# camera.net
KiCad netlist of a schematic drawn in Altium Designer
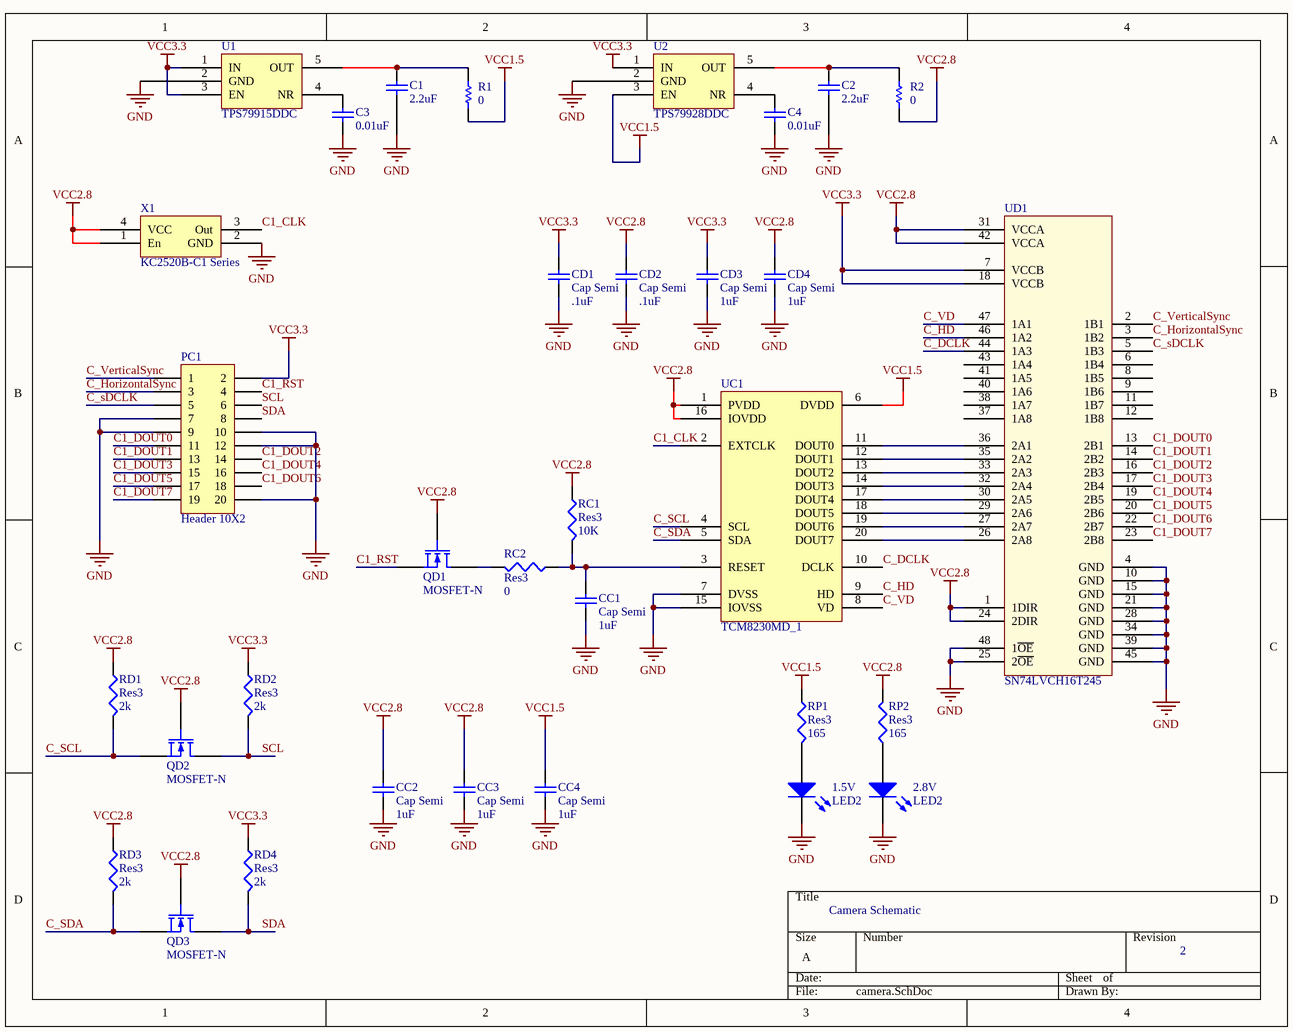
[diagram p0: camera.SchDoc]

(export (version "E")
  (design (tool "Eeschema 10.0.6"))
  (components
    (comp (ref "1.5V")
      (value "LED2")
      (footprint "DIODE1608")
      (description "Typical RED, GREEN, YELLOW, AMBER GaAs LED")
      (fields (field (name "PUBLISHER") "Altium Limited"))
      (libsource (lib "Miscellaneous Devices") (part "LED2"))
    )
    (comp (ref "2.8V")
      (value "LED2")
      (footprint "DIODE1608")
      (description "Typical RED, GREEN, YELLOW, AMBER GaAs LED")
      (fields (field (name "PUBLISHER") "Altium Limited"))
      (libsource (lib "Miscellaneous Devices") (part "LED2"))
    )
    (comp (ref "C1")
      (value "2.2uF")
      (footprint "CAPC1608L")
      (description "Capacitor (Semiconductor SIM Model)")
      (fields (field (name "Comment") "Cap Semi") (field (name "PUBLISHER") "Altium Limited"))
      (libsource (lib "Miscellaneous Devices") (part "Cap Semi"))
    )
    (comp (ref "C2")
      (value "2.2uF")
      (footprint "CAPC1608L")
      (description "Capacitor (Semiconductor SIM Model)")
      (fields (field (name "Comment") "Cap Semi") (field (name "PUBLISHER") "Altium Limited"))
      (libsource (lib "Miscellaneous Devices") (part "Cap Semi"))
    )
    (comp (ref "C3")
      (value "0.01uF")
      (footprint "CAPC1608L")
      (description "Capacitor (Semiconductor SIM Model)")
      (fields (field (name "Comment") "Cap Semi") (field (name "PUBLISHER") "Altium Limited"))
      (libsource (lib "Miscellaneous Devices") (part "Cap Semi"))
    )
    (comp (ref "C4")
      (value "0.01uF")
      (footprint "CAPC1608L")
      (description "Capacitor (Semiconductor SIM Model)")
      (fields (field (name "Comment") "Cap Semi") (field (name "PUBLISHER") "Altium Limited"))
      (libsource (lib "Miscellaneous Devices") (part "Cap Semi"))
    )
    (comp (ref "CC1")
      (value "Cap Semi")
      (footprint "CAPC1608L")
      (description "Capacitor (Semiconductor SIM Model)")
      (fields (field (name "ALTIUM_VALUE") "1uF") (field (name "PUBLISHER") "Altium Limited"))
      (libsource (lib "Miscellaneous Devices") (part "Cap Semi"))
    )
    (comp (ref "CC2")
      (value "Cap Semi")
      (footprint "CAPC1608L")
      (description "Capacitor (Semiconductor SIM Model)")
      (fields (field (name "ALTIUM_VALUE") "1uF") (field (name "PUBLISHER") "Altium Limited"))
      (libsource (lib "Miscellaneous Devices") (part "Cap Semi"))
    )
    (comp (ref "CC3")
      (value "Cap Semi")
      (footprint "CAPC1608L")
      (description "Capacitor (Semiconductor SIM Model)")
      (fields (field (name "ALTIUM_VALUE") "1uF") (field (name "PUBLISHER") "Altium Limited"))
      (libsource (lib "Miscellaneous Devices") (part "Cap Semi"))
    )
    (comp (ref "CC4")
      (value "Cap Semi")
      (footprint "CAPC1608L")
      (description "Capacitor (Semiconductor SIM Model)")
      (fields (field (name "ALTIUM_VALUE") "1uF") (field (name "PUBLISHER") "Altium Limited"))
      (libsource (lib "Miscellaneous Devices") (part "Cap Semi"))
    )
    (comp (ref "CD1")
      (value "Cap Semi")
      (footprint "CAPC1608L")
      (description "Capacitor (Semiconductor SIM Model)")
      (fields (field (name "ALTIUM_VALUE") ".1uF") (field (name "PUBLISHER") "Altium Limited"))
      (libsource (lib "Miscellaneous Devices") (part "Cap Semi"))
    )
    (comp (ref "CD2")
      (value "Cap Semi")
      (footprint "CAPC1608L")
      (description "Capacitor (Semiconductor SIM Model)")
      (fields (field (name "ALTIUM_VALUE") ".1uF") (field (name "PUBLISHER") "Altium Limited"))
      (libsource (lib "Miscellaneous Devices") (part "Cap Semi"))
    )
    (comp (ref "CD3")
      (value "Cap Semi")
      (footprint "CAPC1608L")
      (description "Capacitor (Semiconductor SIM Model)")
      (fields (field (name "ALTIUM_VALUE") "1uF") (field (name "PUBLISHER") "Altium Limited"))
      (libsource (lib "Miscellaneous Devices") (part "Cap Semi"))
    )
    (comp (ref "CD4")
      (value "Cap Semi")
      (footprint "CAPC1608L")
      (description "Capacitor (Semiconductor SIM Model)")
      (fields (field (name "ALTIUM_VALUE") "1uF") (field (name "PUBLISHER") "Altium Limited"))
      (libsource (lib "Miscellaneous Devices") (part "Cap Semi"))
    )
    (comp (ref "PC1")
      (value "Header 10X2")
      (footprint "HDR2X10")
      (description "Header, 10-Pin, Dual row")
      (fields (field (name "PUBLISHER") "Altium Limited"))
      (libsource (lib "Miscellaneous Connectors") (part "Header 10X2"))
    )
    (comp (ref "QD1")
      (value "MOSFET-N")
      (footprint "SOT95P240-3N")
      (description "N-Channel MOSFET")
      (fields (field (name "PUBLISHER") "Altium Limited"))
      (libsource (lib "Miscellaneous Devices") (part "MOSFET-N"))
    )
    (comp (ref "QD2")
      (value "MOSFET-N")
      (footprint "SOT95P240-3N")
      (description "N-Channel MOSFET")
      (fields (field (name "PUBLISHER") "Altium Limited"))
      (libsource (lib "Miscellaneous Devices") (part "MOSFET-N"))
    )
    (comp (ref "QD3")
      (value "MOSFET-N")
      (footprint "SOT95P240-3N")
      (description "N-Channel MOSFET")
      (fields (field (name "PUBLISHER") "Altium Limited"))
      (libsource (lib "Miscellaneous Devices") (part "MOSFET-N"))
    )
    (comp (ref "R1")
      (value "0")
      (footprint "RESC1608L")
      (description "Semiconductor Resistor")
      (fields (field (name "Comment") "Res Semi") (field (name "PUBLISHER") "Altium Limited"))
      (libsource (lib "Miscellaneous Devices") (part "Res Semi"))
    )
    (comp (ref "R2")
      (value "0")
      (footprint "RESC1608L")
      (description "Semiconductor Resistor")
      (fields (field (name "Comment") "Res Semi") (field (name "PUBLISHER") "Altium Limited"))
      (libsource (lib "Miscellaneous Devices") (part "Res Semi"))
    )
    (comp (ref "RC1")
      (value "Res3")
      (footprint "RESC1608L")
      (description "Resistor")
      (fields (field (name "ALTIUM_VALUE") "10K") (field (name "PUBLISHER") "Altium Limited"))
      (libsource (lib "Miscellaneous Devices") (part "Res3"))
    )
    (comp (ref "RC2")
      (value "Res3")
      (footprint "RESC1608L")
      (description "Resistor")
      (fields (field (name "ALTIUM_VALUE") "0") (field (name "PUBLISHER") "Altium Limited"))
      (libsource (lib "Miscellaneous Devices") (part "Res3"))
    )
    (comp (ref "RD1")
      (value "Res3")
      (footprint "RESC1608L")
      (description "Resistor")
      (fields (field (name "ALTIUM_VALUE") "2k") (field (name "PUBLISHER") "Altium Limited"))
      (libsource (lib "Miscellaneous Devices") (part "Res3"))
    )
    (comp (ref "RD2")
      (value "Res3")
      (footprint "RESC1608L")
      (description "Resistor")
      (fields (field (name "ALTIUM_VALUE") "2k") (field (name "PUBLISHER") "Altium Limited"))
      (libsource (lib "Miscellaneous Devices") (part "Res3"))
    )
    (comp (ref "RD3")
      (value "Res3")
      (footprint "RESC1608L")
      (description "Resistor")
      (fields (field (name "ALTIUM_VALUE") "2k") (field (name "PUBLISHER") "Altium Limited"))
      (libsource (lib "Miscellaneous Devices") (part "Res3"))
    )
    (comp (ref "RD4")
      (value "Res3")
      (footprint "RESC1608L")
      (description "Resistor")
      (fields (field (name "ALTIUM_VALUE") "2k") (field (name "PUBLISHER") "Altium Limited"))
      (libsource (lib "Miscellaneous Devices") (part "Res3"))
    )
    (comp (ref "RP1")
      (value "Res3")
      (footprint "RESC1608L")
      (description "Resistor")
      (fields (field (name "ALTIUM_VALUE") "165") (field (name "PUBLISHER") "Altium Limited"))
      (libsource (lib "Miscellaneous Devices") (part "Res3"))
    )
    (comp (ref "RP2")
      (value "Res3")
      (footprint "RESC1608L")
      (description "Resistor")
      (fields (field (name "ALTIUM_VALUE") "165") (field (name "PUBLISHER") "Altium Limited"))
      (libsource (lib "Miscellaneous Devices") (part "Res3"))
    )
    (comp (ref "U1")
      (value "TPS79915DDC")
      (footprint "TSOT23-5")
      (description "200mA, Low Quiescent Current, Ultra-Low Noise, High PSRR  Low Dropout Linear Regulator")
      (libsource (lib "Capstone_Lib") (part "TPS799xxDDC"))
    )
    (comp (ref "U2")
      (value "TPS79928DDC")
      (footprint "TSOT23-5")
      (description "200mA, Low Quiescent Current, Ultra-Low Noise, High PSRR  Low Dropout Linear Regulator")
      (libsource (lib "Capstone_Lib") (part "TPS799xxDDC"))
    )
    (comp (ref "UC1")
      (value "TCM8230MD_1")
      (footprint "TCM8230MD")
      (description "VGA CAMERA MODULE 640x480")
      (libsource (lib "daughterboard") (part "TCM8230MD_1"))
    )
    (comp (ref "UD1")
      (value "SN74LVCH16T245")
      (footprint "SN74LVCH16T245")
      (description "16-bit bus transceiver with voltage regulation.")
      (libsource (lib "daughterboard") (part "SN74LVCH16T245"))
    )
    (comp (ref "X1")
      (value "KC2520B-C1 Series")
      (footprint "KC2520B-C1")
      (description "Standard Oscillator")
      (libsource (lib "Capstone_Lib") (part "KC2520B-C1"))
    )
  )
  (nets
    (net (code "1") (name "/C1_CLK") (class "Default")
      (node (ref "UC1") (pin "2") (pinfunction "EXTCLK_2") (pintype "passive"))
      (node (ref "X1") (pin "3") (pinfunction "Out_3") (pintype "passive"))
    )
    (net (code "2") (name "/C1_DOUT0") (class "Default")
      (node (ref "PC1") (pin "11") (pinfunction "11_11") (pintype "passive"))
      (node (ref "UD1") (pin "13") (pinfunction "2B1_13") (pintype "passive"))
    )
    (net (code "3") (name "/C1_DOUT1") (class "Default")
      (node (ref "PC1") (pin "13") (pinfunction "13_13") (pintype "passive"))
      (node (ref "UD1") (pin "14") (pinfunction "2B2_14") (pintype "passive"))
    )
    (net (code "4") (name "/C1_DOUT2") (class "Default")
      (node (ref "PC1") (pin "14") (pinfunction "14_14") (pintype "passive"))
      (node (ref "UD1") (pin "16") (pinfunction "2B3_16") (pintype "passive"))
    )
    (net (code "5") (name "/C1_DOUT3") (class "Default")
      (node (ref "PC1") (pin "15") (pinfunction "15_15") (pintype "passive"))
      (node (ref "UD1") (pin "17") (pinfunction "2B4_17") (pintype "passive"))
    )
    (net (code "6") (name "/C1_DOUT4") (class "Default")
      (node (ref "PC1") (pin "16") (pinfunction "16_16") (pintype "passive"))
      (node (ref "UD1") (pin "19") (pinfunction "2B5_19") (pintype "passive"))
    )
    (net (code "7") (name "/C1_DOUT5") (class "Default")
      (node (ref "PC1") (pin "17") (pinfunction "17_17") (pintype "passive"))
      (node (ref "UD1") (pin "20") (pinfunction "2B6_20") (pintype "passive"))
    )
    (net (code "8") (name "/C1_DOUT6") (class "Default")
      (node (ref "PC1") (pin "18") (pinfunction "18_18") (pintype "passive"))
      (node (ref "UD1") (pin "22") (pinfunction "2B7_22") (pintype "passive"))
    )
    (net (code "9") (name "/C1_DOUT7") (class "Default")
      (node (ref "PC1") (pin "19") (pinfunction "19_19") (pintype "passive"))
      (node (ref "UD1") (pin "23") (pinfunction "2B8_23") (pintype "passive"))
    )
    (net (code "10") (name "/C1_RST") (class "Default")
      (node (ref "PC1") (pin "4") (pinfunction "4_4") (pintype "passive"))
      (node (ref "QD1") (pin "3") (pinfunction "S_3") (pintype "passive"))
    )
    (net (code "11") (name "/C_DCLK") (class "Default")
      (node (ref "UC1") (pin "10") (pinfunction "DCLK_10") (pintype "passive"))
      (node (ref "UD1") (pin "44") (pinfunction "1A3_44") (pintype "passive"))
    )
    (net (code "12") (name "/C_HD") (class "Default")
      (node (ref "UC1") (pin "9") (pinfunction "HD_9") (pintype "passive"))
      (node (ref "UD1") (pin "46") (pinfunction "1A2_46") (pintype "passive"))
    )
    (net (code "13") (name "/C_HorizontalSync") (class "Default")
      (node (ref "PC1") (pin "3") (pinfunction "3_3") (pintype "passive"))
      (node (ref "UD1") (pin "3") (pinfunction "1B2_3") (pintype "passive"))
    )
    (net (code "14") (name "/C_SCL") (class "Default")
      (node (ref "QD2") (pin "3") (pinfunction "S_3") (pintype "passive"))
      (node (ref "RD1") (pin "2") (pinfunction "2_2") (pintype "passive"))
      (node (ref "UC1") (pin "4") (pinfunction "SCL_4") (pintype "passive"))
    )
    (net (code "15") (name "/C_SDA") (class "Default")
      (node (ref "QD3") (pin "3") (pinfunction "S_3") (pintype "passive"))
      (node (ref "RD3") (pin "2") (pinfunction "2_2") (pintype "passive"))
      (node (ref "UC1") (pin "5") (pinfunction "SDA_5") (pintype "passive"))
    )
    (net (code "16") (name "/C_VD") (class "Default")
      (node (ref "UC1") (pin "8") (pinfunction "VD_8") (pintype "passive"))
      (node (ref "UD1") (pin "47") (pinfunction "1A1_47") (pintype "passive"))
    )
    (net (code "17") (name "/C_VerticalSync") (class "Default")
      (node (ref "PC1") (pin "1") (pinfunction "1_1") (pintype "passive"))
      (node (ref "UD1") (pin "2") (pinfunction "1B1_2") (pintype "passive"))
    )
    (net (code "18") (name "/C_sDCLK") (class "Default")
      (node (ref "PC1") (pin "5") (pinfunction "5_5") (pintype "passive"))
      (node (ref "UD1") (pin "5") (pinfunction "1B3_5") (pintype "passive"))
    )
    (net (code "19") (name "/SCL") (class "Default")
      (node (ref "PC1") (pin "6") (pinfunction "6_6") (pintype "passive"))
      (node (ref "QD2") (pin "1") (pinfunction "D_1") (pintype "passive"))
      (node (ref "RD2") (pin "2") (pinfunction "2_2") (pintype "passive"))
    )
    (net (code "20") (name "/SDA") (class "Default")
      (node (ref "PC1") (pin "8") (pinfunction "8_8") (pintype "passive"))
      (node (ref "QD3") (pin "1") (pinfunction "D_1") (pintype "passive"))
      (node (ref "RD4") (pin "2") (pinfunction "2_2") (pintype "passive"))
    )
    (net (code "21") (name "GND") (class "Default")
      (node (ref "1.5V") (pin "2") (pinfunction "K_2") (pintype "passive"))
      (node (ref "2.8V") (pin "2") (pinfunction "K_2") (pintype "passive"))
      (node (ref "C1") (pin "2") (pinfunction "2_2") (pintype "passive"))
      (node (ref "C2") (pin "2") (pinfunction "2_2") (pintype "passive"))
      (node (ref "C3") (pin "2") (pinfunction "2_2") (pintype "passive"))
      (node (ref "C4") (pin "2") (pinfunction "2_2") (pintype "passive"))
      (node (ref "CC1") (pin "1") (pinfunction "1_1") (pintype "passive"))
      (node (ref "CC2") (pin "1") (pinfunction "1_1") (pintype "passive"))
      (node (ref "CC3") (pin "1") (pinfunction "1_1") (pintype "passive"))
      (node (ref "CC4") (pin "1") (pinfunction "1_1") (pintype "passive"))
      (node (ref "CD1") (pin "1") (pinfunction "1_1") (pintype "passive"))
      (node (ref "CD2") (pin "1") (pinfunction "1_1") (pintype "passive"))
      (node (ref "CD3") (pin "1") (pinfunction "1_1") (pintype "passive"))
      (node (ref "CD4") (pin "1") (pinfunction "1_1") (pintype "passive"))
      (node (ref "PC1") (pin "10") (pinfunction "10_10") (pintype "passive"))
      (node (ref "PC1") (pin "12") (pinfunction "12_12") (pintype "passive"))
      (node (ref "PC1") (pin "20") (pinfunction "20_20") (pintype "passive"))
      (node (ref "PC1") (pin "7") (pinfunction "7_7") (pintype "passive"))
      (node (ref "PC1") (pin "9") (pinfunction "9_9") (pintype "passive"))
      (node (ref "U1") (pin "2") (pinfunction "GND_2") (pintype "passive"))
      (node (ref "U2") (pin "2") (pinfunction "GND_2") (pintype "passive"))
      (node (ref "UC1") (pin "15") (pinfunction "IOVSS_15") (pintype "passive"))
      (node (ref "UC1") (pin "7") (pinfunction "DVSS_7") (pintype "passive"))
      (node (ref "UD1") (pin "10") (pinfunction "GND_10") (pintype "passive"))
      (node (ref "UD1") (pin "15") (pinfunction "GND_15") (pintype "passive"))
      (node (ref "UD1") (pin "21") (pinfunction "GND_21") (pintype "passive"))
      (node (ref "UD1") (pin "25") (pinfunction "2~{OE}_25") (pintype "passive"))
      (node (ref "UD1") (pin "28") (pinfunction "GND_28") (pintype "passive"))
      (node (ref "UD1") (pin "34") (pinfunction "GND_34") (pintype "passive"))
      (node (ref "UD1") (pin "39") (pinfunction "GND_39") (pintype "passive"))
      (node (ref "UD1") (pin "4") (pinfunction "GND_4") (pintype "passive"))
      (node (ref "UD1") (pin "45") (pinfunction "GND_45") (pintype "passive"))
      (node (ref "UD1") (pin "48") (pinfunction "1~{OE}_48") (pintype "passive"))
      (node (ref "X1") (pin "2") (pinfunction "GND_2") (pintype "passive"))
    )
    (net (code "22") (name "Net-(1.5V-A)") (class "Default")
      (node (ref "1.5V") (pin "1") (pinfunction "A_1") (pintype "passive"))
      (node (ref "RP1") (pin "2") (pinfunction "2_2") (pintype "passive"))
    )
    (net (code "23") (name "Net-(2.8V-A)") (class "Default")
      (node (ref "2.8V") (pin "1") (pinfunction "A_1") (pintype "passive"))
      (node (ref "RP2") (pin "1") (pinfunction "1_1") (pintype "passive"))
    )
    (net (code "24") (name "Net-(QD1-D)") (class "Default")
      (node (ref "QD1") (pin "1") (pinfunction "D_1") (pintype "passive"))
      (node (ref "RC2") (pin "1") (pinfunction "1_1") (pintype "passive"))
    )
    (net (code "25") (name "Net-(U1-NR)") (class "Default")
      (node (ref "C3") (pin "1") (pinfunction "1_1") (pintype "passive"))
      (node (ref "U1") (pin "4") (pinfunction "NR_4") (pintype "passive"))
    )
    (net (code "26") (name "Net-(U1-OUT)") (class "Default")
      (node (ref "C1") (pin "1") (pinfunction "1_1") (pintype "passive"))
      (node (ref "R1") (pin "1") (pinfunction "1_1") (pintype "passive"))
      (node (ref "U1") (pin "5") (pinfunction "OUT_5") (pintype "passive"))
    )
    (net (code "27") (name "Net-(U2-NR)") (class "Default")
      (node (ref "C4") (pin "1") (pinfunction "1_1") (pintype "passive"))
      (node (ref "U2") (pin "4") (pinfunction "NR_4") (pintype "passive"))
    )
    (net (code "28") (name "Net-(U2-OUT)") (class "Default")
      (node (ref "C2") (pin "1") (pinfunction "1_1") (pintype "passive"))
      (node (ref "R2") (pin "1") (pinfunction "1_1") (pintype "passive"))
      (node (ref "U2") (pin "5") (pinfunction "OUT_5") (pintype "passive"))
    )
    (net (code "29") (name "Net-(UC1-DOUT0)") (class "Default")
      (node (ref "UC1") (pin "11") (pinfunction "DOUT0_11") (pintype "passive"))
      (node (ref "UD1") (pin "36") (pinfunction "2A1_36") (pintype "passive"))
    )
    (net (code "30") (name "Net-(UC1-DOUT1)") (class "Default")
      (node (ref "UC1") (pin "12") (pinfunction "DOUT1_12") (pintype "passive"))
      (node (ref "UD1") (pin "35") (pinfunction "2A2_35") (pintype "passive"))
    )
    (net (code "31") (name "Net-(UC1-DOUT2)") (class "Default")
      (node (ref "UC1") (pin "13") (pinfunction "DOUT2_13") (pintype "passive"))
      (node (ref "UD1") (pin "33") (pinfunction "2A3_33") (pintype "passive"))
    )
    (net (code "32") (name "Net-(UC1-DOUT3)") (class "Default")
      (node (ref "UC1") (pin "14") (pinfunction "DOUT3_14") (pintype "passive"))
      (node (ref "UD1") (pin "32") (pinfunction "2A4_32") (pintype "passive"))
    )
    (net (code "33") (name "Net-(UC1-DOUT4)") (class "Default")
      (node (ref "UC1") (pin "17") (pinfunction "DOUT4_17") (pintype "passive"))
      (node (ref "UD1") (pin "30") (pinfunction "2A5_30") (pintype "passive"))
    )
    (net (code "34") (name "Net-(UC1-DOUT5)") (class "Default")
      (node (ref "UC1") (pin "18") (pinfunction "DOUT5_18") (pintype "passive"))
      (node (ref "UD1") (pin "29") (pinfunction "2A6_29") (pintype "passive"))
    )
    (net (code "35") (name "Net-(UC1-DOUT6)") (class "Default")
      (node (ref "UC1") (pin "19") (pinfunction "DOUT6_19") (pintype "passive"))
      (node (ref "UD1") (pin "27") (pinfunction "2A7_27") (pintype "passive"))
    )
    (net (code "36") (name "Net-(UC1-DOUT7)") (class "Default")
      (node (ref "UC1") (pin "20") (pinfunction "DOUT7_20") (pintype "passive"))
      (node (ref "UD1") (pin "26") (pinfunction "2A8_26") (pintype "passive"))
    )
    (net (code "37") (name "Net-(UC1-RESET)") (class "Default")
      (node (ref "CC1") (pin "2") (pinfunction "2_2") (pintype "passive"))
      (node (ref "RC1") (pin "1") (pinfunction "1_1") (pintype "passive"))
      (node (ref "RC2") (pin "2") (pinfunction "2_2") (pintype "passive"))
      (node (ref "UC1") (pin "3") (pinfunction "RESET_3") (pintype "passive"))
    )
    (net (code "38") (name "VCC1.5") (class "Default")
      (node (ref "CC4") (pin "2") (pinfunction "2_2") (pintype "passive"))
      (node (ref "R1") (pin "2") (pinfunction "2_2") (pintype "passive"))
      (node (ref "RP1") (pin "1") (pinfunction "1_1") (pintype "passive"))
      (node (ref "U2") (pin "3") (pinfunction "EN_3") (pintype "passive"))
      (node (ref "UC1") (pin "6") (pinfunction "DVDD_6") (pintype "passive"))
    )
    (net (code "39") (name "VCC2.8") (class "Default")
      (node (ref "CC2") (pin "2") (pinfunction "2_2") (pintype "passive"))
      (node (ref "CC3") (pin "2") (pinfunction "2_2") (pintype "passive"))
      (node (ref "CD2") (pin "2") (pinfunction "2_2") (pintype "passive"))
      (node (ref "CD4") (pin "2") (pinfunction "2_2") (pintype "passive"))
      (node (ref "QD1") (pin "2") (pinfunction "G_2") (pintype "passive"))
      (node (ref "QD2") (pin "2") (pinfunction "G_2") (pintype "passive"))
      (node (ref "QD3") (pin "2") (pinfunction "G_2") (pintype "passive"))
      (node (ref "R2") (pin "2") (pinfunction "2_2") (pintype "passive"))
      (node (ref "RC1") (pin "2") (pinfunction "2_2") (pintype "passive"))
      (node (ref "RD1") (pin "1") (pinfunction "1_1") (pintype "passive"))
      (node (ref "RD3") (pin "1") (pinfunction "1_1") (pintype "passive"))
      (node (ref "RP2") (pin "2") (pinfunction "2_2") (pintype "passive"))
      (node (ref "UC1") (pin "1") (pinfunction "PVDD_1") (pintype "passive"))
      (node (ref "UC1") (pin "16") (pinfunction "IOVDD_16") (pintype "passive"))
      (node (ref "UD1") (pin "1") (pinfunction "1DIR_1") (pintype "passive"))
      (node (ref "UD1") (pin "24") (pinfunction "2DIR_24") (pintype "passive"))
      (node (ref "UD1") (pin "31") (pinfunction "VCCA_31") (pintype "passive"))
      (node (ref "UD1") (pin "42") (pinfunction "VCCA_42") (pintype "passive"))
      (node (ref "X1") (pin "1") (pinfunction "En_1") (pintype "passive"))
      (node (ref "X1") (pin "4") (pinfunction "VCC_4") (pintype "passive"))
    )
    (net (code "40") (name "VCC3.3") (class "Default")
      (node (ref "CD1") (pin "2") (pinfunction "2_2") (pintype "passive"))
      (node (ref "CD3") (pin "2") (pinfunction "2_2") (pintype "passive"))
      (node (ref "PC1") (pin "2") (pinfunction "2_2") (pintype "passive"))
      (node (ref "RD2") (pin "1") (pinfunction "1_1") (pintype "passive"))
      (node (ref "RD4") (pin "1") (pinfunction "1_1") (pintype "passive"))
      (node (ref "U1") (pin "1") (pinfunction "IN_1") (pintype "passive"))
      (node (ref "U1") (pin "3") (pinfunction "EN_3") (pintype "passive"))
      (node (ref "U2") (pin "1") (pinfunction "IN_1") (pintype "passive"))
      (node (ref "UD1") (pin "18") (pinfunction "VCCB_18") (pintype "passive"))
      (node (ref "UD1") (pin "7") (pinfunction "VCCB_7") (pintype "passive"))
    )
    (net (code "41") (name "unconnected-(UD1-1A4-Pad43)") (class "Default")
      (node (ref "UD1") (pin "43") (pinfunction "1A4_43") (pintype "passive"))
    )
    (net (code "42") (name "unconnected-(UD1-1A5-Pad41)") (class "Default")
      (node (ref "UD1") (pin "41") (pinfunction "1A5_41") (pintype "passive"))
    )
    (net (code "43") (name "unconnected-(UD1-1A6-Pad40)") (class "Default")
      (node (ref "UD1") (pin "40") (pinfunction "1A6_40") (pintype "passive"))
    )
    (net (code "44") (name "unconnected-(UD1-1A7-Pad38)") (class "Default")
      (node (ref "UD1") (pin "38") (pinfunction "1A7_38") (pintype "passive"))
    )
    (net (code "45") (name "unconnected-(UD1-1A8-Pad37)") (class "Default")
      (node (ref "UD1") (pin "37") (pinfunction "1A8_37") (pintype "passive"))
    )
    (net (code "46") (name "unconnected-(UD1-1B4-Pad6)") (class "Default")
      (node (ref "UD1") (pin "6") (pinfunction "1B4_6") (pintype "passive"))
    )
    (net (code "47") (name "unconnected-(UD1-1B5-Pad8)") (class "Default")
      (node (ref "UD1") (pin "8") (pinfunction "1B5_8") (pintype "passive"))
    )
    (net (code "48") (name "unconnected-(UD1-1B6-Pad9)") (class "Default")
      (node (ref "UD1") (pin "9") (pinfunction "1B6_9") (pintype "passive"))
    )
    (net (code "49") (name "unconnected-(UD1-1B7-Pad11)") (class "Default")
      (node (ref "UD1") (pin "11") (pinfunction "1B7_11") (pintype "passive"))
    )
    (net (code "50") (name "unconnected-(UD1-1B8-Pad12)") (class "Default")
      (node (ref "UD1") (pin "12") (pinfunction "1B8_12") (pintype "passive"))
    )
  )
)
